# cookie-mouse.net
KiCad netlist of a schematic drawn in EAGLE
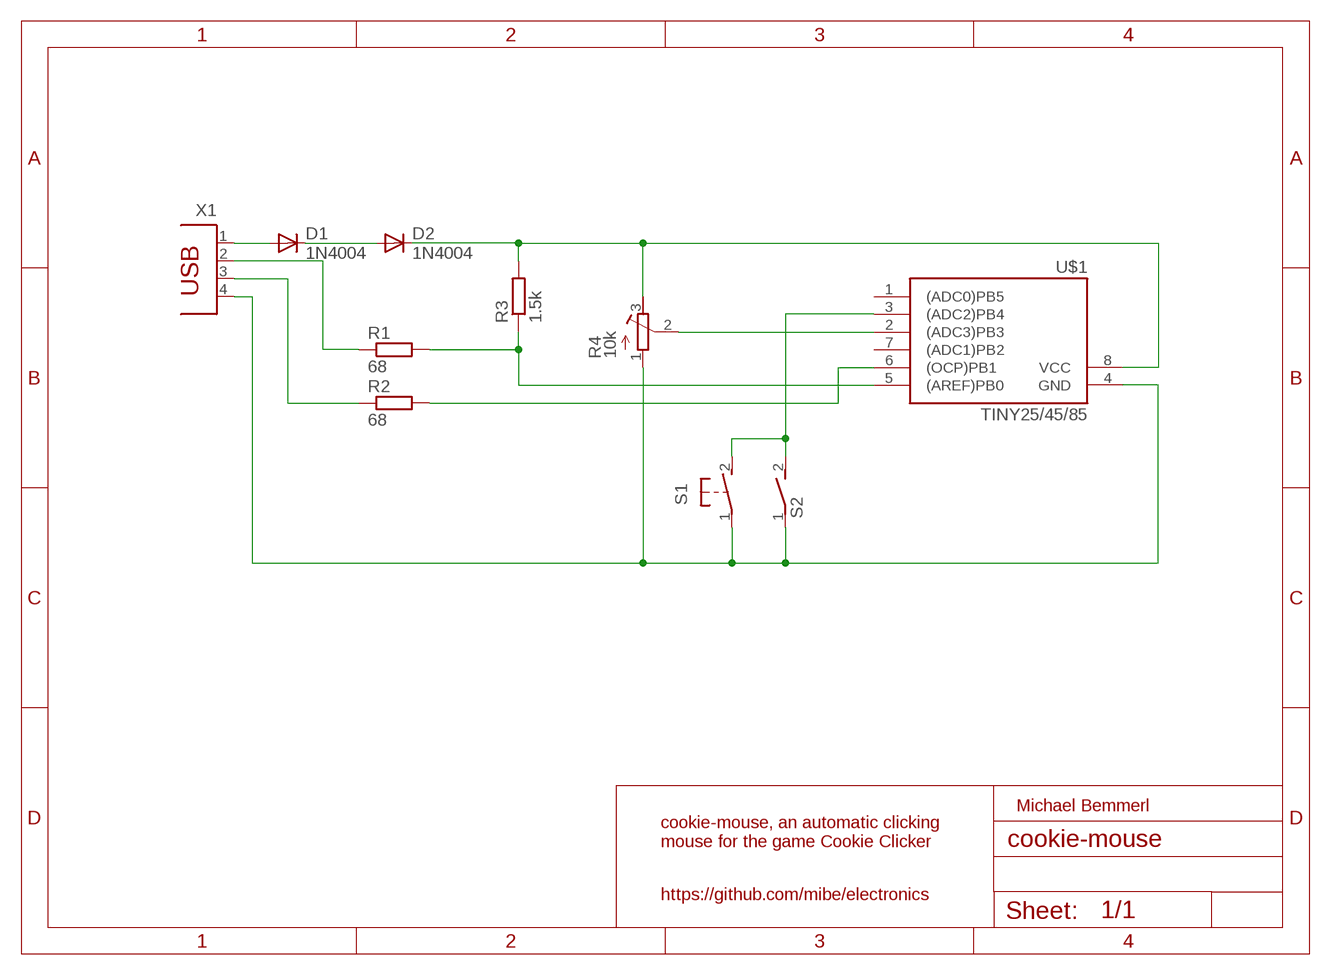
[diagram p0: schematic, sheet 1]

(export (version "E")
  (design (tool "Eeschema 10.0.6"))
  (components
    (comp (ref "D1")
      (value "1N4004")
      (footprint "eagle-import:DO41-10")
      (libsource (lib "eagle-import") (part "1N4004"))
    )
    (comp (ref "D2")
      (value "1N4004")
      (footprint "eagle-import:DO41-10")
      (libsource (lib "eagle-import") (part "1N4004"))
    )
    (comp (ref "R1")
      (value "68")
      (footprint "eagle-import:0207_10")
      (libsource (lib "eagle-import") (part "R-EU_0207/10"))
    )
    (comp (ref "R2")
      (value "68")
      (footprint "eagle-import:0207_10")
      (libsource (lib "eagle-import") (part "R-EU_0207/10"))
    )
    (comp (ref "R3")
      (value "1.5k")
      (footprint "eagle-import:0207_10")
      (libsource (lib "eagle-import") (part "R-EU_0207/10"))
    )
    (comp (ref "R4")
      (value "10k")
      (footprint "eagle-import:RTRIM4G_J")
      (libsource (lib "eagle-import") (part "R-TRIMM4G/J"))
    )
    (comp (ref "S1")
      (value "31-XX")
      (footprint "eagle-import:B3F-31XX")
      (fields (field (name "MPN") "B3F-3100"))
      (libsource (lib "eagle-import") (part "31-XX"))
    )
    (comp (ref "S2")
      (value "DS01E")
      (footprint "eagle-import:DS-01")
      (libsource (lib "eagle-import") (part "DS01E"))
    )
    (comp (ref "U$1")
      (value "TINY25/45/85")
      (footprint "eagle-import:DIL08")
      (libsource (lib "eagle-import") (part "TINY25/45/85"))
    )
    (comp (ref "X1")
      (value "PN61729")
      (footprint "eagle-import:PN61729")
      (libsource (lib "eagle-import") (part "PN61729"))
    )
  )
  (nets
    (net (code "1") (name "Net-(D1-PadA)") (class "Default")
      (node (ref "D1") (pin "A") (pinfunction "A_A") (pintype "passive"))
      (node (ref "X1") (pin "1") (pinfunction "1_1") (pintype "passive"))
    )
    (net (code "2") (name "Net-(D1-PadC)") (class "Default")
      (node (ref "D1") (pin "C") (pinfunction "C_C") (pintype "passive"))
      (node (ref "D2") (pin "A") (pinfunction "A_A") (pintype "passive"))
    )
    (net (code "3") (name "Net-(R1-Pad1)") (class "Default")
      (node (ref "R1") (pin "1") (pinfunction "1_1") (pintype "passive"))
      (node (ref "X1") (pin "2") (pinfunction "2_2") (pintype "passive"))
    )
    (net (code "4") (name "Net-(R2-Pad1)") (class "Default")
      (node (ref "R2") (pin "1") (pinfunction "1_1") (pintype "passive"))
      (node (ref "X1") (pin "3") (pinfunction "3_3") (pintype "passive"))
    )
    (net (code "5") (name "Net-(R4-A)") (class "Default")
      (node (ref "D2") (pin "C") (pinfunction "C_C") (pintype "passive"))
      (node (ref "R3") (pin "2") (pinfunction "2_2") (pintype "passive"))
      (node (ref "R4") (pin "3") (pinfunction "A_3") (pintype "passive"))
      (node (ref "U$1") (pin "8") (pinfunction "VCC_8") (pintype "power_in"))
    )
    (net (code "6") (name "Net-(R4-E)") (class "Default")
      (node (ref "R4") (pin "1") (pinfunction "E_1") (pintype "passive"))
      (node (ref "S1") (pin "1") (pinfunction "P_1") (pintype "passive"))
      (node (ref "S2") (pin "1") (pinfunction "1_1") (pintype "passive"))
      (node (ref "U$1") (pin "4") (pinfunction "GND_4") (pintype "power_in"))
      (node (ref "X1") (pin "4") (pinfunction "4_4") (pintype "passive"))
    )
    (net (code "7") (name "Net-(R4-S)") (class "Default")
      (node (ref "R4") (pin "2") (pinfunction "S_2") (pintype "passive"))
      (node (ref "U$1") (pin "2") (pinfunction "(ADC3)PB3_2") (pintype "bidirectional"))
    )
    (net (code "8") (name "Net-(S1-S)") (class "Default")
      (node (ref "S1") (pin "2") (pinfunction "S_2") (pintype "passive"))
      (node (ref "S2") (pin "2") (pinfunction "2_2") (pintype "passive"))
      (node (ref "U$1") (pin "3") (pinfunction "(ADC2)PB4_3") (pintype "bidirectional"))
    )
    (net (code "9") (name "Net-(U$1-(AREF)PB0)") (class "Default")
      (node (ref "R1") (pin "2") (pinfunction "2_2") (pintype "passive"))
      (node (ref "R3") (pin "1") (pinfunction "1_1") (pintype "passive"))
      (node (ref "U$1") (pin "5") (pinfunction "(AREF)PB0_5") (pintype "bidirectional"))
    )
    (net (code "10") (name "Net-(U$1-(OCP)PB1)") (class "Default")
      (node (ref "R2") (pin "2") (pinfunction "2_2") (pintype "passive"))
      (node (ref "U$1") (pin "6") (pinfunction "(OCP)PB1_6") (pintype "bidirectional"))
    )
    (net (code "11") (name "unconnected-(U$1-(ADC0)PB5-Pad1)") (class "Default")
      (node (ref "U$1") (pin "1") (pinfunction "(ADC0)PB5_1") (pintype "bidirectional"))
    )
    (net (code "12") (name "unconnected-(U$1-(ADC1)PB2-Pad7)") (class "Default")
      (node (ref "U$1") (pin "7") (pinfunction "(ADC1)PB2_7") (pintype "bidirectional"))
    )
  )
)
